# MAR.net
KiCad netlist of a schematic drawn in EasyEDA Pro
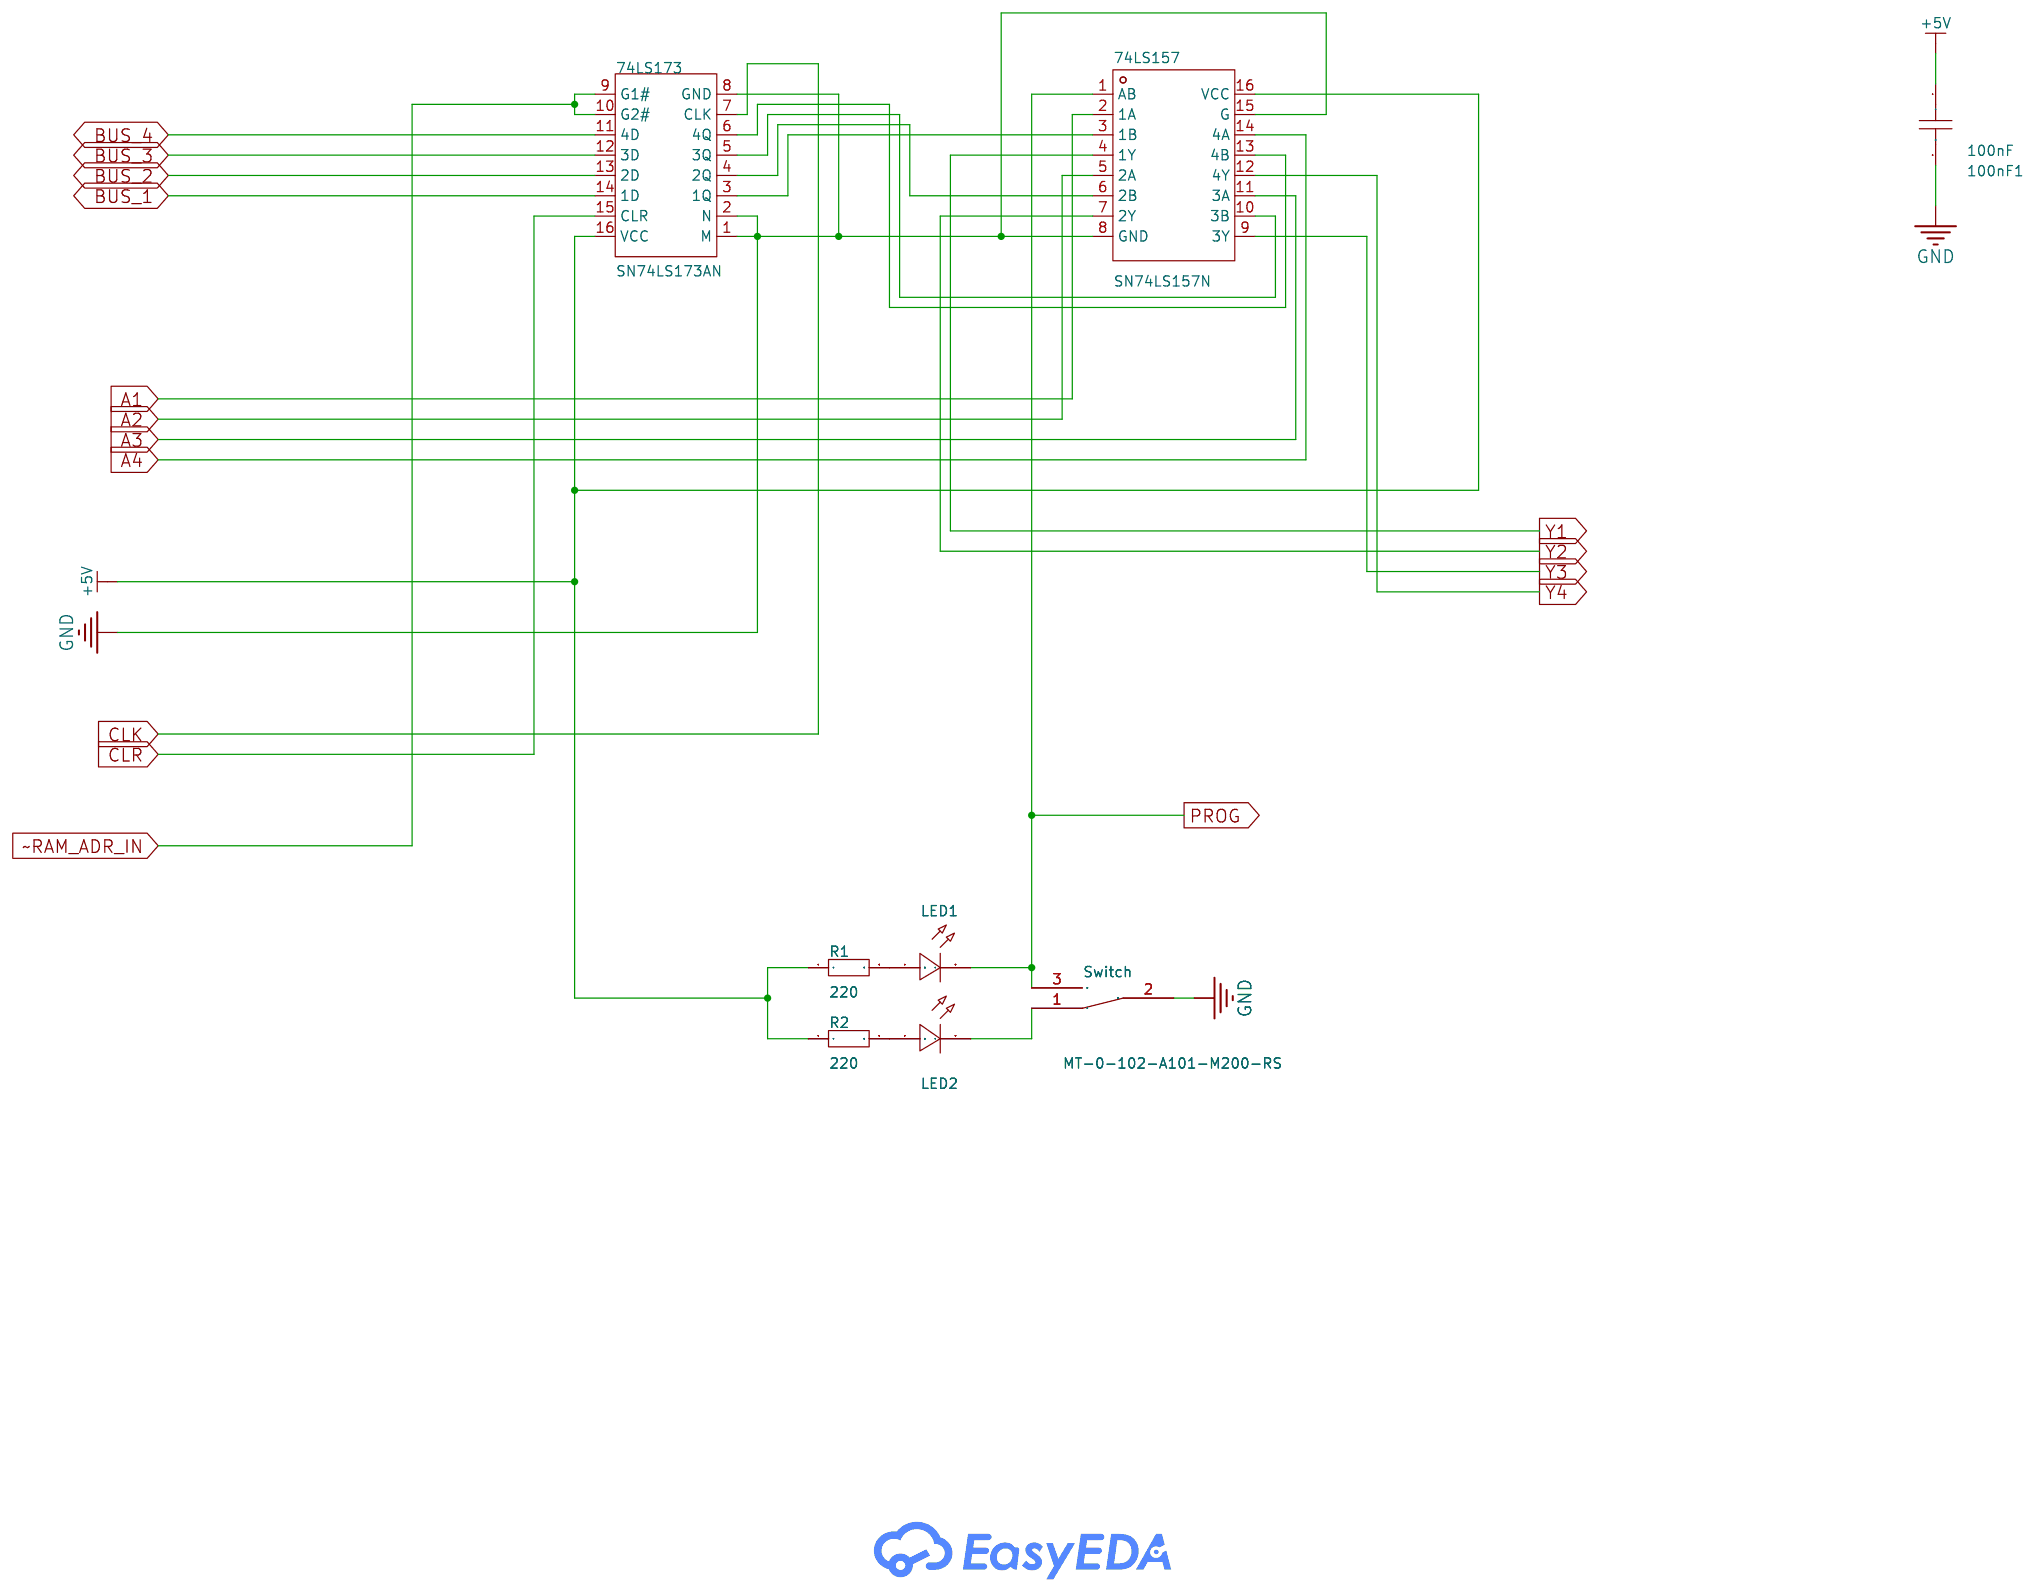
[diagram p0: schematic sheet]

(export (version "E")
  (design (tool "Eeschema 10.0.6"))
  (components
    (comp (ref "74LS157")
      (value "SN74LS157N")
      (footprint "easyedapro:DIP-16_16P-L20.2-W6.6-P2.54-LS7.6-BL")
      (fields (field (name "Manufacturer") "TI(德州仪器)"))
      (libsource (lib "easyedapro") (part "SN74LS157N"))
    )
    (comp (ref "74LS173")
      (value "SN74LS173AN")
      (footprint "easyedapro:PDIP-16_L19.3-W6.4-P2.54-LS7.94-BL")
      (fields (field (name "Manufacturer") "TI(德州仪器)"))
      (libsource (lib "easyedapro") (part "SN74LS173AN"))
    )
    (comp (ref "100nF1")
      (value "100nF")
      (footprint "easyedapro:CAP-TH_L8.5-W5.0-P5.00-D1.2")
      (fields (field (name "Manufacturer Part") "CT4-0805B104K500F3") (field (name "Manufacturer") "FH(风华)"))
      (libsource (lib "easyedapro") (part "CT4-0805B104K500F3"))
    )
    (comp (ref "LED1")
      (value "~")
      (footprint "easyedapro:LED-TH_BD5.8-P2.54-FD")
      (libsource (lib "easyedapro") (part "LED_TH-R"))
    )
    (comp (ref "LED2")
      (value "~")
      (footprint "easyedapro:LED-TH_BD5.8-P2.54-FD")
      (libsource (lib "easyedapro") (part "LED_TH-R"))
    )
    (comp (ref "R1")
      (value "220")
      (footprint "easyedapro:R_AXIAL-0.4")
      (libsource (lib "easyedapro") (part "Res"))
    )
    (comp (ref "R2")
      (value "220")
      (footprint "easyedapro:R_AXIAL-0.4")
      (libsource (lib "easyedapro") (part "Res"))
    )
    (comp (ref "Switch")
      (value "MT-0-102-A101-M200-RS")
      (footprint "easyedapro:SW-TH_MT-0-103-A101-M200-RS")
      (fields (field (name "Manufacturer") "YUEN FUNG(源丰)"))
      (libsource (lib "easyedapro") (part "MT-0-102-A101-M200-RS+PJ"))
    )
  )
  (nets
    (net (code "1") (name "+5V") (class "Default")
      (node (ref "100nF1") (pin "1") (pinfunction "1_1") (pintype "unspecified"))
      (node (ref "74LS157") (pin "16") (pinfunction "VCC_16") (pintype "unspecified"))
      (node (ref "74LS173") (pin "16") (pinfunction "VCC_16") (pintype "unspecified"))
      (node (ref "R1") (pin "1") (pinfunction "1_1") (pintype "input"))
      (node (ref "R2") (pin "1") (pinfunction "1_1") (pintype "input"))
    )
    (net (code "2") (name "A1") (class "Default")
      (node (ref "74LS157") (pin "2") (pinfunction "1A_2") (pintype "unspecified"))
    )
    (net (code "3") (name "A2") (class "Default")
      (node (ref "74LS157") (pin "5") (pinfunction "2A_5") (pintype "unspecified"))
    )
    (net (code "4") (name "A3") (class "Default")
      (node (ref "74LS157") (pin "11") (pinfunction "3A_11") (pintype "unspecified"))
    )
    (net (code "5") (name "A4") (class "Default")
      (node (ref "74LS157") (pin "14") (pinfunction "4A_14") (pintype "unspecified"))
    )
    (net (code "6") (name "BUS_1") (class "Default")
      (node (ref "74LS173") (pin "14") (pinfunction "1D_14") (pintype "unspecified"))
    )
    (net (code "7") (name "BUS_2") (class "Default")
      (node (ref "74LS173") (pin "13") (pinfunction "2D_13") (pintype "unspecified"))
    )
    (net (code "8") (name "BUS_3") (class "Default")
      (node (ref "74LS173") (pin "12") (pinfunction "3D_12") (pintype "unspecified"))
    )
    (net (code "9") (name "BUS_4") (class "Default")
      (node (ref "74LS173") (pin "11") (pinfunction "4D_11") (pintype "unspecified"))
    )
    (net (code "10") (name "CLK") (class "Default")
      (node (ref "74LS173") (pin "7") (pinfunction "CLK_7") (pintype "unspecified"))
    )
    (net (code "11") (name "CLR") (class "Default")
      (node (ref "74LS173") (pin "15") (pinfunction "CLR_15") (pintype "unspecified"))
    )
    (net (code "12") (name "GND") (class "Default")
      (node (ref "100nF1") (pin "2") (pinfunction "2_2") (pintype "unspecified"))
      (node (ref "74LS157") (pin "15") (pinfunction "G_15") (pintype "unspecified"))
      (node (ref "74LS157") (pin "8") (pinfunction "GND_8") (pintype "unspecified"))
      (node (ref "74LS173") (pin "1") (pinfunction "M_1") (pintype "unspecified"))
      (node (ref "74LS173") (pin "2") (pinfunction "N_2") (pintype "unspecified"))
      (node (ref "74LS173") (pin "8") (pinfunction "GND_8") (pintype "unspecified"))
      (node (ref "Switch") (pin "2") (pinfunction "2_2") (pintype "unspecified"))
    )
    (net (code "13") (name "Net-(74LS157-1B)") (class "Default")
      (node (ref "74LS157") (pin "3") (pinfunction "1B_3") (pintype "unspecified"))
      (node (ref "74LS173") (pin "3") (pinfunction "1Q_3") (pintype "unspecified"))
    )
    (net (code "14") (name "Net-(74LS157-2B)") (class "Default")
      (node (ref "74LS157") (pin "6") (pinfunction "2B_6") (pintype "unspecified"))
      (node (ref "74LS173") (pin "4") (pinfunction "2Q_4") (pintype "unspecified"))
    )
    (net (code "15") (name "Net-(74LS157-3B)") (class "Default")
      (node (ref "74LS157") (pin "10") (pinfunction "3B_10") (pintype "unspecified"))
      (node (ref "74LS173") (pin "5") (pinfunction "3Q_5") (pintype "unspecified"))
    )
    (net (code "16") (name "Net-(74LS157-4B)") (class "Default")
      (node (ref "74LS157") (pin "13") (pinfunction "4B_13") (pintype "unspecified"))
      (node (ref "74LS173") (pin "6") (pinfunction "4Q_6") (pintype "unspecified"))
    )
    (net (code "17") (name "Net-(LED1-C)") (class "Default")
      (node (ref "LED1") (pin "1") (pinfunction "C_1") (pintype "input"))
      (node (ref "R1") (pin "2") (pinfunction "2_2") (pintype "input"))
    )
    (net (code "18") (name "Net-(LED2-A)") (class "Default")
      (node (ref "LED2") (pin "2") (pinfunction "A_2") (pintype "input"))
      (node (ref "Switch") (pin "1") (pinfunction "1_1") (pintype "unspecified"))
    )
    (net (code "19") (name "Net-(LED2-C)") (class "Default")
      (node (ref "LED2") (pin "1") (pinfunction "C_1") (pintype "input"))
      (node (ref "R2") (pin "2") (pinfunction "2_2") (pintype "input"))
    )
    (net (code "20") (name "PROG") (class "Default")
      (node (ref "74LS157") (pin "1") (pinfunction "AB_1") (pintype "unspecified"))
      (node (ref "LED1") (pin "2") (pinfunction "A_2") (pintype "input"))
      (node (ref "Switch") (pin "3") (pinfunction "3_3") (pintype "unspecified"))
    )
    (net (code "21") (name "Y1") (class "Default")
      (node (ref "74LS157") (pin "4") (pinfunction "1Y_4") (pintype "unspecified"))
    )
    (net (code "22") (name "Y2") (class "Default")
      (node (ref "74LS157") (pin "7") (pinfunction "2Y_7") (pintype "unspecified"))
    )
    (net (code "23") (name "Y3") (class "Default")
      (node (ref "74LS157") (pin "9") (pinfunction "3Y_9") (pintype "unspecified"))
    )
    (net (code "24") (name "Y4") (class "Default")
      (node (ref "74LS157") (pin "12") (pinfunction "4Y_12") (pintype "unspecified"))
    )
    (net (code "25") (name "~RAM_ADR_IN") (class "Default")
      (node (ref "74LS173") (pin "10") (pinfunction "G2#_10") (pintype "unspecified"))
      (node (ref "74LS173") (pin "9") (pinfunction "G1#_9") (pintype "unspecified"))
    )
  )
)
